# Isolated_Gate_Driver_Bias_Supply_Schemat.net
KiCad netlist of a schematic drawn in Altium Designer
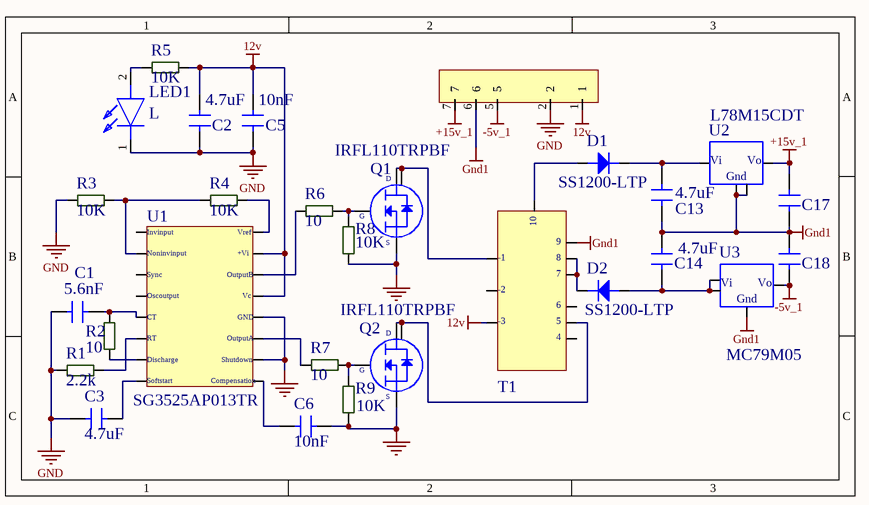
[diagram p0: Isolated Gate Driver Bias Supply Schematic.SchDoc]

(export (version "E")
  (design (tool "Eeschema 10.0.6"))
  (components
    (comp (ref "7")
      (value "7")
      (footprint "Isolated Gate Driver Bias Supply pcblib:SIP7")
      (libsource (lib "Isolated Gate Driver Bias Supply schematic lib") (part "sip7"))
    )
    (comp (ref "C1")
      (value "5.6nF")
      (footprint "Cap1206")
      (description "Cap Ceramic 10uF 50V X5R 10% SMD 1206 85C T/R")
      (fields
        (field (name "MANUFACTURER") "Samsung")
        (field (name "MANUFACTURER PART NUMBER") "CL31A106KBHNNNE")
      )
      (libsource (lib "Isolated Gate Driver Bias Supply schematic lib") (part "CL31A106KBHNNNE"))
    )
    (comp (ref "C2")
      (value "4.7uF")
      (footprint "Cap1206")
      (description "Cap Ceramic 10uF 50V X5R 10% SMD 1206 85C T/R")
      (fields
        (field (name "MANUFACTURER") "Samsung")
        (field (name "MANUFACTURER PART NUMBER") "CL31A106KBHNNNE")
      )
      (libsource (lib "Isolated Gate Driver Bias Supply schematic lib") (part "CL31A106KBHNNNE"))
    )
    (comp (ref "C3")
      (value "4.7uF")
      (footprint "Cap1206")
      (description "Cap Ceramic 10uF 50V X5R 10% SMD 1206 85C T/R")
      (fields
        (field (name "MANUFACTURER") "Samsung")
        (field (name "MANUFACTURER PART NUMBER") "CL31A106KBHNNNE")
      )
      (libsource (lib "Isolated Gate Driver Bias Supply schematic lib") (part "CL31A106KBHNNNE"))
    )
    (comp (ref "C5")
      (value "10nF")
      (footprint "Cap1206")
      (description "Cap Ceramic 10uF 50V X5R 10% SMD 1206 85C T/R")
      (fields
        (field (name "MANUFACTURER") "Samsung")
        (field (name "MANUFACTURER PART NUMBER") "CL31A106KBHNNNE")
      )
      (libsource (lib "Isolated Gate Driver Bias Supply schematic lib") (part "CL31A106KBHNNNE"))
    )
    (comp (ref "C6")
      (value "10nF")
      (footprint "Cap1206")
      (description "Cap Ceramic 10uF 50V X5R 10% SMD 1206 85C T/R")
      (fields
        (field (name "MANUFACTURER") "Samsung")
        (field (name "MANUFACTURER PART NUMBER") "CL31A106KBHNNNE")
      )
      (libsource (lib "Isolated Gate Driver Bias Supply schematic lib") (part "CL31A106KBHNNNE"))
    )
    (comp (ref "C13")
      (value "4.7uF")
      (footprint "Cap1206")
      (description "Cap Ceramic 10uF 50V X5R 10% SMD 1206 85C T/R")
      (fields
        (field (name "MANUFACTURER") "Samsung")
        (field (name "MANUFACTURER PART NUMBER") "CL31A106KBHNNNE")
      )
      (libsource (lib "Isolated Gate Driver Bias Supply schematic lib") (part "CL31A106KBHNNNE"))
    )
    (comp (ref "C14")
      (value "4.7uF")
      (footprint "Cap1206")
      (description "Cap Ceramic 10uF 50V X5R 10% SMD 1206 85C T/R")
      (fields
        (field (name "MANUFACTURER") "Samsung")
        (field (name "MANUFACTURER PART NUMBER") "CL31A106KBHNNNE")
      )
      (libsource (lib "Isolated Gate Driver Bias Supply schematic lib") (part "CL31A106KBHNNNE"))
    )
    (comp (ref "C17")
      (value "CL31A106KBHNNNE")
      (footprint "Cap1206")
      (description "Cap Ceramic 10uF 50V X5R 10% SMD 1206 85C T/R")
      (fields (field (name "MANUFACTURER") "Samsung") (field (name "TOLERANCE") "10%"))
      (libsource (lib "Isolated Gate Driver Bias Supply schematic lib") (part "CL31A106KBHNNNE"))
    )
    (comp (ref "C18")
      (value "CL31A106KBHNNNE")
      (footprint "Cap1206")
      (description "Cap Ceramic 10uF 50V X5R 10% SMD 1206 85C T/R")
      (fields (field (name "MANUFACTURER") "Samsung") (field (name "TOLERANCE") "10%"))
      (libsource (lib "Isolated Gate Driver Bias Supply schematic lib") (part "CL31A106KBHNNNE"))
    )
    (comp (ref "D1")
      (value "SS1200-LTP")
      (footprint "DO-214AC")
      (description "DIODE SCHOTTKY 200V 1A DO214AC")
      (fields (field (name "MANUFACTURER") "MCC"))
      (libsource (lib "Isolated Gate Driver Bias Supply schematic lib") (part "SS1200-LTP"))
    )
    (comp (ref "D2")
      (value "SS1200-LTP")
      (footprint "DO-214AC")
      (description "DIODE SCHOTTKY 200V 1A DO214AC")
      (fields (field (name "MANUFACTURER") "MCC"))
      (libsource (lib "Isolated Gate Driver Bias Supply schematic lib") (part "SS1200-LTP"))
    )
    (comp (ref "LED1")
      (value "L")
      (footprint "Mobile Charger:L-1206")
      (description "LED")
      (fields
        (field (name "MANUFACTURER_PART_NUMBER") "LTST-C150KGKT")
        (field (name "MOUSER PART NUMBER") "859-LTST-C150KGKT")
      )
      (libsource (lib "Isolated Gate Driver Bias Supply schematic lib") (part "LTST-C150KGKT"))
    )
    (comp (ref "Q1")
      (value "IRFL110TRPBF")
      (footprint "SOT223")
      (description "Trans MOSFET N-CH 100V 1.5A 4-Pin(3+Tab) T/R")
      (fields (field (name "MANUFACTURER") "Vishay") (field (name "VOLTAGE") "100V"))
      (libsource (lib "Isolated Gate Driver Bias Supply schematic lib") (part "IRFL110TRPBF"))
    )
    (comp (ref "Q2")
      (value "IRFL110TRPBF")
      (footprint "SOT223")
      (description "Trans MOSFET N-CH 100V 1.5A 4-Pin(3+Tab) T/R")
      (fields (field (name "MANUFACTURER") "Vishay") (field (name "VOLTAGE") "100V"))
      (libsource (lib "Isolated Gate Driver Bias Supply schematic lib") (part "IRFL110TRPBF"))
    )
    (comp (ref "R1")
      (value "2.2k")
      (footprint "RES1206")
      (description "RES 0 OHM JUMPER 1/4W 1206")
      (fields
        (field (name "MANUFACTURER") "Stackpole Electronics")
        (field (name "MANUFACTURER PART NUMBER") "RMCF1206ZT0R00")
      )
      (libsource (lib "Isolated Gate Driver Bias Supply schematic lib") (part "RMCF1206ZT0R00"))
    )
    (comp (ref "R2")
      (value "10")
      (footprint "RES1206")
      (description "RES 0 OHM JUMPER 1/4W 1206")
      (fields
        (field (name "MANUFACTURER") "Stackpole Electronics")
        (field (name "MANUFACTURER PART NUMBER") "RMCF1206ZT0R00")
      )
      (libsource (lib "Isolated Gate Driver Bias Supply schematic lib") (part "RMCF1206ZT0R00"))
    )
    (comp (ref "R3")
      (value "10K")
      (footprint "RES1206")
      (description "RES 0 OHM JUMPER 1/4W 1206")
      (fields
        (field (name "MANUFACTURER") "Stackpole Electronics")
        (field (name "MANUFACTURER PART NUMBER") "RMCF1206ZT0R00")
      )
      (libsource (lib "Isolated Gate Driver Bias Supply schematic lib") (part "RMCF1206ZT0R00"))
    )
    (comp (ref "R4")
      (value "10K")
      (footprint "RES1206")
      (description "RES 0 OHM JUMPER 1/4W 1206")
      (fields
        (field (name "MANUFACTURER") "Stackpole Electronics")
        (field (name "MANUFACTURER PART NUMBER") "RMCF1206ZT0R00")
      )
      (libsource (lib "Isolated Gate Driver Bias Supply schematic lib") (part "RMCF1206ZT0R00"))
    )
    (comp (ref "R5")
      (value "10K")
      (footprint "RES1206")
      (description "RES 0 OHM JUMPER 1/4W 1206")
      (fields
        (field (name "MANUFACTURER") "Stackpole Electronics")
        (field (name "MANUFACTURER PART NUMBER") "RMCF1206ZT0R00")
      )
      (libsource (lib "Isolated Gate Driver Bias Supply schematic lib") (part "RMCF1206ZT0R00"))
    )
    (comp (ref "R6")
      (value "10")
      (footprint "RES1206")
      (description "RES 0 OHM JUMPER 1/4W 1206")
      (fields
        (field (name "MANUFACTURER") "Stackpole Electronics")
        (field (name "MANUFACTURER PART NUMBER") "RMCF1206ZT0R00")
      )
      (libsource (lib "Isolated Gate Driver Bias Supply schematic lib") (part "RMCF1206ZT0R00"))
    )
    (comp (ref "R7")
      (value "10")
      (footprint "RES1206")
      (description "RES 0 OHM JUMPER 1/4W 1206")
      (fields
        (field (name "MANUFACTURER") "Stackpole Electronics")
        (field (name "MANUFACTURER PART NUMBER") "RMCF1206ZT0R00")
      )
      (libsource (lib "Isolated Gate Driver Bias Supply schematic lib") (part "RMCF1206ZT0R00"))
    )
    (comp (ref "R8")
      (value "10K")
      (footprint "RES1206")
      (description "RES 0 OHM JUMPER 1/4W 1206")
      (fields
        (field (name "MANUFACTURER") "Stackpole Electronics")
        (field (name "MANUFACTURER PART NUMBER") "RMCF1206ZT0R00")
      )
      (libsource (lib "Isolated Gate Driver Bias Supply schematic lib") (part "RMCF1206ZT0R00"))
    )
    (comp (ref "R9")
      (value "10K")
      (footprint "RES1206")
      (description "RES 0 OHM JUMPER 1/4W 1206")
      (fields
        (field (name "MANUFACTURER") "Stackpole Electronics")
        (field (name "MANUFACTURER PART NUMBER") "RMCF1206ZT0R00")
      )
      (libsource (lib "Isolated Gate Driver Bias Supply schematic lib") (part "RMCF1206ZT0R00"))
    )
    (comp (ref "T1")
      (value "EE2006Transformer")
      (footprint "EE2006")
      (libsource (lib "Isolated Gate Driver Bias Supply schematic lib") (part "EE2006Transformer"))
    )
    (comp (ref "U1")
      (value "SG3525AP013TR")
      (footprint "SOIC16N SG3525")
      (description "IC REG CTRLR BCK/PSH-PULL 16SOIC")
      (fields (field (name "MANUFACTURER") "STMicroelectronics"))
      (libsource (lib "Isolated Gate Driver Bias Supply schematic lib") (part "SG3525AP013TR"))
    )
    (comp (ref "U2")
      (value "L78M15CDT")
      (footprint "sot89")
      (description "Linear Voltage Regulators 15V 0.5A Positive")
      (fields (field (name "MANUFACTURER") "STMicroelectronics"))
      (libsource (lib "Isolated Gate Driver Bias Supply schematic lib") (part "L78M15CDT"))
    )
    (comp (ref "U3")
      (value "MC79M05")
      (footprint "sot89")
      (description "ON SEMICONDUCTOR - MC79M05CDTRKG - NEGATIVE VOLTAGE REGULATOR, -5V, DPAK-3")
      (fields
        (field (name "MANUFACTURER") "ON Semiconductor")
        (field (name "MANUFACTURER PART NUMBER") "MC79M05CDTRKG")
      )
      (libsource (lib "Isolated Gate Driver Bias Supply schematic lib") (part "MC79M05CDTRKG"))
    )
  )
  (nets
    (net (code "1") (name "+15v_1") (class "Default")
      (node (ref "7") (pin "7") (pinfunction "7_7") (pintype "passive"))
      (node (ref "C17") (pin "1") (pinfunction "1_1") (pintype "passive"))
      (node (ref "U2") (pin "1") (pinfunction "1_1") (pintype "passive"))
    )
    (net (code "2") (name "-5v_1") (class "Default")
      (node (ref "7") (pin "5") (pinfunction "5_5") (pintype "passive"))
      (node (ref "C18") (pin "2") (pinfunction "2_2") (pintype "passive"))
      (node (ref "U3") (pin "3") (pinfunction "3_3") (pintype "passive"))
    )
    (net (code "3") (name "12v") (class "Default")
      (node (ref "7") (pin "1") (pinfunction "1_1") (pintype "passive"))
      (node (ref "C2") (pin "1") (pinfunction "1_1") (pintype "passive"))
      (node (ref "C5") (pin "1") (pinfunction "1_1") (pintype "passive"))
      (node (ref "R5") (pin "1") (pinfunction "1_1") (pintype "passive"))
      (node (ref "T1") (pin "3") (pinfunction "3_3") (pintype "passive"))
      (node (ref "U1") (pin "13") (pinfunction "13_13") (pintype "passive"))
      (node (ref "U1") (pin "15") (pinfunction "15_15") (pintype "passive"))
    )
    (net (code "4") (name "GND") (class "Default")
      (node (ref "7") (pin "2") (pinfunction "2_2") (pintype "passive"))
      (node (ref "C1") (pin "2") (pinfunction "2_2") (pintype "passive"))
      (node (ref "C2") (pin "2") (pinfunction "2_2") (pintype "passive"))
      (node (ref "C3") (pin "1") (pinfunction "1_1") (pintype "passive"))
      (node (ref "C5") (pin "2") (pinfunction "2_2") (pintype "passive"))
      (node (ref "C6") (pin "1") (pinfunction "1_1") (pintype "passive"))
      (node (ref "LED1") (pin "1") (pinfunction "K_1") (pintype "passive"))
      (node (ref "Q1") (pin "3") (pinfunction "3_3") (pintype "passive"))
      (node (ref "Q2") (pin "3") (pinfunction "3_3") (pintype "passive"))
      (node (ref "R1") (pin "1") (pinfunction "1_1") (pintype "passive"))
      (node (ref "R3") (pin "2") (pinfunction "2_2") (pintype "passive"))
      (node (ref "R8") (pin "1") (pinfunction "1_1") (pintype "passive"))
      (node (ref "R9") (pin "2") (pinfunction "2_2") (pintype "passive"))
      (node (ref "U1") (pin "10") (pinfunction "10_10") (pintype "passive"))
      (node (ref "U1") (pin "12") (pinfunction "12_12") (pintype "passive"))
    )
    (net (code "5") (name "Gnd1") (class "Default")
      (node (ref "7") (pin "6") (pinfunction "6_6") (pintype "passive"))
      (node (ref "C13") (pin "2") (pinfunction "2_2") (pintype "passive"))
      (node (ref "C14") (pin "1") (pinfunction "1_1") (pintype "passive"))
      (node (ref "C17") (pin "2") (pinfunction "2_2") (pintype "passive"))
      (node (ref "C18") (pin "1") (pinfunction "1_1") (pintype "passive"))
      (node (ref "T1") (pin "9") (pinfunction "9_9") (pintype "passive"))
      (node (ref "U2") (pin "2") (pinfunction "2_2") (pintype "passive"))
      (node (ref "U2") (pin "4") (pinfunction "4_4") (pintype "passive"))
      (node (ref "U3") (pin "1") (pinfunction "1_1") (pintype "passive"))
    )
    (net (code "6") (name "Net-(C1-Pad1)") (class "Default")
      (node (ref "C1") (pin "1") (pinfunction "1_1") (pintype "passive"))
      (node (ref "R2") (pin "1") (pinfunction "1_1") (pintype "passive"))
      (node (ref "U1") (pin "5") (pinfunction "5_5") (pintype "passive"))
    )
    (net (code "7") (name "Net-(C3-Pad2)") (class "Default")
      (node (ref "C3") (pin "2") (pinfunction "2_2") (pintype "passive"))
      (node (ref "U1") (pin "8") (pinfunction "8_8") (pintype "passive"))
    )
    (net (code "8") (name "Net-(C6-Pad2)") (class "Default")
      (node (ref "C6") (pin "2") (pinfunction "2_2") (pintype "passive"))
      (node (ref "U1") (pin "9") (pinfunction "9_9") (pintype "passive"))
    )
    (net (code "9") (name "Net-(C13-Pad1)") (class "Default")
      (node (ref "C13") (pin "1") (pinfunction "1_1") (pintype "passive"))
      (node (ref "D1") (pin "k") (pinfunction "k_k") (pintype "passive"))
      (node (ref "U2") (pin "3") (pinfunction "3_3") (pintype "passive"))
    )
    (net (code "10") (name "Net-(C14-Pad2)") (class "Default")
      (node (ref "C14") (pin "2") (pinfunction "2_2") (pintype "passive"))
      (node (ref "D2") (pin "a") (pinfunction "a_a") (pintype "passive"))
      (node (ref "U3") (pin "2") (pinfunction "2_2") (pintype "passive"))
    )
    (net (code "11") (name "Net-(D1-Pada)") (class "Default")
      (node (ref "D1") (pin "a") (pinfunction "a_a") (pintype "passive"))
      (node (ref "T1") (pin "10") (pinfunction "10_10") (pintype "passive"))
    )
    (net (code "12") (name "Net-(D2-Padk)") (class "Default")
      (node (ref "D2") (pin "k") (pinfunction "k_k") (pintype "passive"))
      (node (ref "T1") (pin "7") (pinfunction "7_7") (pintype "passive"))
      (node (ref "T1") (pin "8") (pinfunction "8_8") (pintype "passive"))
    )
    (net (code "13") (name "Net-(LED1-A)") (class "Default")
      (node (ref "LED1") (pin "2") (pinfunction "A_2") (pintype "passive"))
      (node (ref "R5") (pin "2") (pinfunction "2_2") (pintype "passive"))
    )
    (net (code "14") (name "Net-(Q1-Pad1)") (class "Default")
      (node (ref "Q1") (pin "1") (pinfunction "1_1") (pintype "passive"))
      (node (ref "R6") (pin "1") (pinfunction "1_1") (pintype "passive"))
      (node (ref "R8") (pin "2") (pinfunction "2_2") (pintype "passive"))
    )
    (net (code "15") (name "Net-(Q1-Pad2)") (class "Default")
      (node (ref "Q1") (pin "2") (pinfunction "2_2") (pintype "passive"))
      (node (ref "Q1") (pin "4") (pinfunction "4_4") (pintype "passive"))
      (node (ref "T1") (pin "1") (pinfunction "1_1") (pintype "passive"))
    )
    (net (code "16") (name "Net-(Q2-Pad1)") (class "Default")
      (node (ref "Q2") (pin "1") (pinfunction "1_1") (pintype "passive"))
      (node (ref "R7") (pin "1") (pinfunction "1_1") (pintype "passive"))
      (node (ref "R9") (pin "1") (pinfunction "1_1") (pintype "passive"))
    )
    (net (code "17") (name "Net-(Q2-Pad2)") (class "Default")
      (node (ref "Q2") (pin "2") (pinfunction "2_2") (pintype "passive"))
      (node (ref "Q2") (pin "4") (pinfunction "4_4") (pintype "passive"))
      (node (ref "T1") (pin "5") (pinfunction "5_5") (pintype "passive"))
    )
    (net (code "18") (name "Net-(R1-Pad2)") (class "Default")
      (node (ref "R1") (pin "2") (pinfunction "2_2") (pintype "passive"))
      (node (ref "U1") (pin "6") (pinfunction "6_6") (pintype "passive"))
    )
    (net (code "19") (name "Net-(R2-Pad2)") (class "Default")
      (node (ref "R2") (pin "2") (pinfunction "2_2") (pintype "passive"))
      (node (ref "U1") (pin "7") (pinfunction "7_7") (pintype "passive"))
    )
    (net (code "20") (name "Net-(R3-Pad1)") (class "Default")
      (node (ref "R3") (pin "1") (pinfunction "1_1") (pintype "passive"))
      (node (ref "R4") (pin "2") (pinfunction "2_2") (pintype "passive"))
      (node (ref "U1") (pin "2") (pinfunction "2_2") (pintype "passive"))
    )
    (net (code "21") (name "Net-(R4-Pad1)") (class "Default")
      (node (ref "R4") (pin "1") (pinfunction "1_1") (pintype "passive"))
      (node (ref "U1") (pin "16") (pinfunction "16_16") (pintype "passive"))
    )
    (net (code "22") (name "Net-(R6-Pad2)") (class "Default")
      (node (ref "R6") (pin "2") (pinfunction "2_2") (pintype "passive"))
      (node (ref "U1") (pin "14") (pinfunction "14_14") (pintype "passive"))
    )
    (net (code "23") (name "Net-(R7-Pad2)") (class "Default")
      (node (ref "R7") (pin "2") (pinfunction "2_2") (pintype "passive"))
      (node (ref "U1") (pin "11") (pinfunction "11_11") (pintype "passive"))
    )
    (net (code "24") (name "unconnected-(T1-Pad2)") (class "Default")
      (node (ref "T1") (pin "2") (pinfunction "2_2") (pintype "passive"))
    )
    (net (code "25") (name "unconnected-(T1-Pad4)") (class "Default")
      (node (ref "T1") (pin "4") (pinfunction "4_4") (pintype "passive"))
    )
    (net (code "26") (name "unconnected-(T1-Pad6)") (class "Default")
      (node (ref "T1") (pin "6") (pinfunction "6_6") (pintype "passive"))
    )
    (net (code "27") (name "unconnected-(U1-Pad1)") (class "Default")
      (node (ref "U1") (pin "1") (pinfunction "1_1") (pintype "passive"))
    )
    (net (code "28") (name "unconnected-(U1-Pad3)") (class "Default")
      (node (ref "U1") (pin "3") (pinfunction "3_3") (pintype "passive"))
    )
    (net (code "29") (name "unconnected-(U1-Pad4)") (class "Default")
      (node (ref "U1") (pin "4") (pinfunction "4_4") (pintype "passive"))
    )
  )
)
